# cadiz_mb_20131224.net
KiCad netlist of a schematic drawn in EAGLE
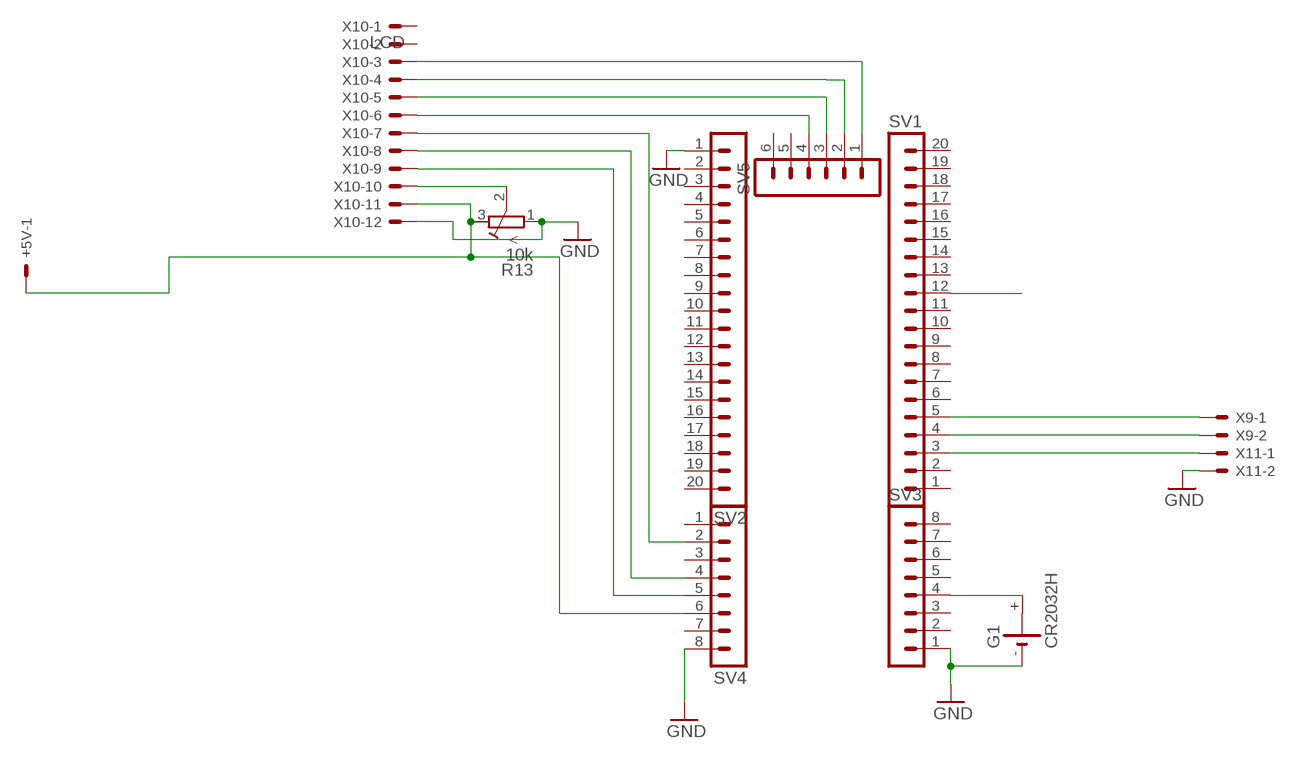
[diagram p0: schematic, sheet 1]

(export (version "E")
  (design (tool "Eeschema 10.0.6"))
  (components
    (comp (ref "+5V")
      (value "22-23-2021")
      (footprint "eagle-import:22-23-2021")
      (fields (field (name "MF") "MOLEX"))
      (libsource (lib "eagle-import") (part "22-23-2021"))
    )
    (comp (ref "G1")
      (value "CR2032H")
      (footprint "eagle-import:CR2032H")
      (libsource (lib "eagle-import") (part "CR2032H"))
    )
    (comp (ref "R13")
      (value "10k")
      (footprint "eagle-import:RTRIM3374")
      (libsource (lib "eagle-import") (part "R-TRIMM3374"))
    )
    (comp (ref "SV1")
      (value "MA20-1")
      (footprint "eagle-import:MA20-1")
      (libsource (lib "eagle-import") (part "MA20-1"))
    )
    (comp (ref "SV2")
      (value "MA20-1")
      (footprint "eagle-import:MA20-1")
      (libsource (lib "eagle-import") (part "MA20-1"))
    )
    (comp (ref "SV3")
      (value "MA08-1")
      (footprint "eagle-import:MA08-1")
      (libsource (lib "eagle-import") (part "MA08-1"))
    )
    (comp (ref "SV4")
      (value "MA08-1")
      (footprint "eagle-import:MA08-1")
      (libsource (lib "eagle-import") (part "MA08-1"))
    )
    (comp (ref "SV5")
      (value "MA06-1")
      (footprint "eagle-import:MA06-1")
      (libsource (lib "eagle-import") (part "MA06-1"))
    )
    (comp (ref "X9")
      (value "22-23-2021")
      (footprint "eagle-import:22-23-2021")
      (fields (field (name "MF") "MOLEX"))
      (libsource (lib "eagle-import") (part "22-23-2021"))
    )
    (comp (ref "X10")
      (value "LCD")
      (footprint "eagle-import:22-23-2121")
      (fields (field (name "MF") "MOLEX") (field (name "MPN") "22-23-2121"))
      (libsource (lib "eagle-import") (part "22-23-2121"))
    )
    (comp (ref "X11")
      (value "22-23-2021")
      (footprint "eagle-import:22-23-2021")
      (fields (field (name "MF") "MOLEX"))
      (libsource (lib "eagle-import") (part "22-23-2021"))
    )
  )
  (nets
    (net (code "1") (name "GND") (class "Default")
      (node (ref "G1") (pin "-") (pinfunction "-_-") (pintype "passive"))
      (node (ref "R13") (pin "1") (pinfunction "E_1") (pintype "passive"))
      (node (ref "SV2") (pin "1") (pinfunction "1_1") (pintype "passive"))
      (node (ref "SV3") (pin "1") (pinfunction "1_1") (pintype "passive"))
      (node (ref "SV4") (pin "8") (pinfunction "8_8") (pintype "passive"))
      (node (ref "X10") (pin "12") (pinfunction "S_12") (pintype "passive"))
      (node (ref "X11") (pin "2") (pinfunction "S_2") (pintype "passive"))
    )
    (net (code "2") (name "Net-(+5VA-S)") (class "Default")
      (node (ref "+5V") (pin "1") (pinfunction "S_1") (pintype "passive"))
      (node (ref "R13") (pin "3") (pinfunction "A_3") (pintype "passive"))
      (node (ref "SV4") (pin "6") (pinfunction "6_6") (pintype "passive"))
      (node (ref "X10") (pin "11") (pinfunction "S_11") (pintype "passive"))
    )
    (net (code "3") (name "Net-(G1-Pad+)") (class "Default")
      (node (ref "G1") (pin "+") (pinfunction "+_+") (pintype "passive"))
      (node (ref "SV3") (pin "4") (pinfunction "4_4") (pintype "passive"))
    )
    (net (code "4") (name "Net-(R13-S)") (class "Default")
      (node (ref "R13") (pin "2") (pinfunction "S_2") (pintype "passive"))
      (node (ref "X10") (pin "10") (pinfunction "S_10") (pintype "passive"))
    )
    (net (code "5") (name "Net-(X9A-S)") (class "Default")
      (node (ref "SV1") (pin "5") (pinfunction "5_5") (pintype "passive"))
      (node (ref "X9") (pin "1") (pinfunction "S_1") (pintype "passive"))
    )
    (net (code "6") (name "Net-(X9B-S)") (class "Default")
      (node (ref "SV1") (pin "4") (pinfunction "4_4") (pintype "passive"))
      (node (ref "X9") (pin "2") (pinfunction "S_2") (pintype "passive"))
    )
    (net (code "7") (name "Net-(X10F-S)") (class "Default")
      (node (ref "SV5") (pin "1") (pinfunction "1_1") (pintype "passive"))
      (node (ref "X10") (pin "3") (pinfunction "S_3") (pintype "passive"))
    )
    (net (code "8") (name "Net-(X10G-S)") (class "Default")
      (node (ref "SV5") (pin "2") (pinfunction "2_2") (pintype "passive"))
      (node (ref "X10") (pin "4") (pinfunction "S_4") (pintype "passive"))
    )
    (net (code "9") (name "Net-(X10H-S)") (class "Default")
      (node (ref "SV5") (pin "3") (pinfunction "3_3") (pintype "passive"))
      (node (ref "X10") (pin "5") (pinfunction "S_5") (pintype "passive"))
    )
    (net (code "10") (name "Net-(X10I-S)") (class "Default")
      (node (ref "SV5") (pin "4") (pinfunction "4_4") (pintype "passive"))
      (node (ref "X10") (pin "6") (pinfunction "S_6") (pintype "passive"))
    )
    (net (code "11") (name "Net-(X10J-S)") (class "Default")
      (node (ref "SV4") (pin "2") (pinfunction "2_2") (pintype "passive"))
      (node (ref "X10") (pin "7") (pinfunction "S_7") (pintype "passive"))
    )
    (net (code "12") (name "Net-(X10K-S)") (class "Default")
      (node (ref "SV4") (pin "4") (pinfunction "4_4") (pintype "passive"))
      (node (ref "X10") (pin "8") (pinfunction "S_8") (pintype "passive"))
    )
    (net (code "13") (name "Net-(X10L-S)") (class "Default")
      (node (ref "SV4") (pin "5") (pinfunction "5_5") (pintype "passive"))
      (node (ref "X10") (pin "9") (pinfunction "S_9") (pintype "passive"))
    )
    (net (code "14") (name "Net-(X11A-S)") (class "Default")
      (node (ref "SV1") (pin "3") (pinfunction "3_3") (pintype "passive"))
      (node (ref "X11") (pin "1") (pinfunction "S_1") (pintype "passive"))
    )
    (net (code "15") (name "unconnected-(G1-+-Pad+@1)") (class "Default")
      (node (ref "G1") (pin "+@1") (pinfunction "+_+@1") (pintype "passive"))
    )
    (net (code "16") (name "unconnected-(SV1-Pad1)") (class "Default")
      (node (ref "SV1") (pin "1") (pinfunction "1_1") (pintype "passive"))
    )
    (net (code "17") (name "unconnected-(SV1-Pad2)") (class "Default")
      (node (ref "SV1") (pin "2") (pinfunction "2_2") (pintype "passive"))
    )
    (net (code "18") (name "unconnected-(SV1-Pad6)") (class "Default")
      (node (ref "SV1") (pin "6") (pinfunction "6_6") (pintype "passive"))
    )
    (net (code "19") (name "unconnected-(SV1-Pad7)") (class "Default")
      (node (ref "SV1") (pin "7") (pinfunction "7_7") (pintype "passive"))
    )
    (net (code "20") (name "unconnected-(SV1-Pad8)") (class "Default")
      (node (ref "SV1") (pin "8") (pinfunction "8_8") (pintype "passive"))
    )
    (net (code "21") (name "unconnected-(SV1-Pad9)") (class "Default")
      (node (ref "SV1") (pin "9") (pinfunction "9_9") (pintype "passive"))
    )
    (net (code "22") (name "unconnected-(SV1-Pad10)") (class "Default")
      (node (ref "SV1") (pin "10") (pinfunction "10_10") (pintype "passive"))
    )
    (net (code "23") (name "unconnected-(SV1-Pad11)") (class "Default")
      (node (ref "SV1") (pin "11") (pinfunction "11_11") (pintype "passive"))
    )
    (net (code "24") (name "unconnected-(SV1-Pad12)") (class "Default")
      (node (ref "SV1") (pin "12") (pinfunction "12_12") (pintype "passive"))
    )
    (net (code "25") (name "unconnected-(SV1-Pad13)") (class "Default")
      (node (ref "SV1") (pin "13") (pinfunction "13_13") (pintype "passive"))
    )
    (net (code "26") (name "unconnected-(SV1-Pad14)") (class "Default")
      (node (ref "SV1") (pin "14") (pinfunction "14_14") (pintype "passive"))
    )
    (net (code "27") (name "unconnected-(SV1-Pad15)") (class "Default")
      (node (ref "SV1") (pin "15") (pinfunction "15_15") (pintype "passive"))
    )
    (net (code "28") (name "unconnected-(SV1-Pad16)") (class "Default")
      (node (ref "SV1") (pin "16") (pinfunction "16_16") (pintype "passive"))
    )
    (net (code "29") (name "unconnected-(SV1-Pad17)") (class "Default")
      (node (ref "SV1") (pin "17") (pinfunction "17_17") (pintype "passive"))
    )
    (net (code "30") (name "unconnected-(SV1-Pad18)") (class "Default")
      (node (ref "SV1") (pin "18") (pinfunction "18_18") (pintype "passive"))
    )
    (net (code "31") (name "unconnected-(SV1-Pad19)") (class "Default")
      (node (ref "SV1") (pin "19") (pinfunction "19_19") (pintype "passive"))
    )
    (net (code "32") (name "unconnected-(SV1-Pad20)") (class "Default")
      (node (ref "SV1") (pin "20") (pinfunction "20_20") (pintype "passive"))
    )
    (net (code "33") (name "unconnected-(SV2-Pad2)") (class "Default")
      (node (ref "SV2") (pin "2") (pinfunction "2_2") (pintype "passive"))
    )
    (net (code "34") (name "unconnected-(SV2-Pad3)") (class "Default")
      (node (ref "SV2") (pin "3") (pinfunction "3_3") (pintype "passive"))
    )
    (net (code "35") (name "unconnected-(SV2-Pad4)") (class "Default")
      (node (ref "SV2") (pin "4") (pinfunction "4_4") (pintype "passive"))
    )
    (net (code "36") (name "unconnected-(SV2-Pad5)") (class "Default")
      (node (ref "SV2") (pin "5") (pinfunction "5_5") (pintype "passive"))
    )
    (net (code "37") (name "unconnected-(SV2-Pad6)") (class "Default")
      (node (ref "SV2") (pin "6") (pinfunction "6_6") (pintype "passive"))
    )
    (net (code "38") (name "unconnected-(SV2-Pad7)") (class "Default")
      (node (ref "SV2") (pin "7") (pinfunction "7_7") (pintype "passive"))
    )
    (net (code "39") (name "unconnected-(SV2-Pad8)") (class "Default")
      (node (ref "SV2") (pin "8") (pinfunction "8_8") (pintype "passive"))
    )
    (net (code "40") (name "unconnected-(SV2-Pad9)") (class "Default")
      (node (ref "SV2") (pin "9") (pinfunction "9_9") (pintype "passive"))
    )
    (net (code "41") (name "unconnected-(SV2-Pad10)") (class "Default")
      (node (ref "SV2") (pin "10") (pinfunction "10_10") (pintype "passive"))
    )
    (net (code "42") (name "unconnected-(SV2-Pad11)") (class "Default")
      (node (ref "SV2") (pin "11") (pinfunction "11_11") (pintype "passive"))
    )
    (net (code "43") (name "unconnected-(SV2-Pad12)") (class "Default")
      (node (ref "SV2") (pin "12") (pinfunction "12_12") (pintype "passive"))
    )
    (net (code "44") (name "unconnected-(SV2-Pad13)") (class "Default")
      (node (ref "SV2") (pin "13") (pinfunction "13_13") (pintype "passive"))
    )
    (net (code "45") (name "unconnected-(SV2-Pad14)") (class "Default")
      (node (ref "SV2") (pin "14") (pinfunction "14_14") (pintype "passive"))
    )
    (net (code "46") (name "unconnected-(SV2-Pad15)") (class "Default")
      (node (ref "SV2") (pin "15") (pinfunction "15_15") (pintype "passive"))
    )
    (net (code "47") (name "unconnected-(SV2-Pad16)") (class "Default")
      (node (ref "SV2") (pin "16") (pinfunction "16_16") (pintype "passive"))
    )
    (net (code "48") (name "unconnected-(SV2-Pad17)") (class "Default")
      (node (ref "SV2") (pin "17") (pinfunction "17_17") (pintype "passive"))
    )
    (net (code "49") (name "unconnected-(SV2-Pad18)") (class "Default")
      (node (ref "SV2") (pin "18") (pinfunction "18_18") (pintype "passive"))
    )
    (net (code "50") (name "unconnected-(SV2-Pad19)") (class "Default")
      (node (ref "SV2") (pin "19") (pinfunction "19_19") (pintype "passive"))
    )
    (net (code "51") (name "unconnected-(SV2-Pad20)") (class "Default")
      (node (ref "SV2") (pin "20") (pinfunction "20_20") (pintype "passive"))
    )
    (net (code "52") (name "unconnected-(SV3-Pad2)") (class "Default")
      (node (ref "SV3") (pin "2") (pinfunction "2_2") (pintype "passive"))
    )
    (net (code "53") (name "unconnected-(SV3-Pad3)") (class "Default")
      (node (ref "SV3") (pin "3") (pinfunction "3_3") (pintype "passive"))
    )
    (net (code "54") (name "unconnected-(SV3-Pad5)") (class "Default")
      (node (ref "SV3") (pin "5") (pinfunction "5_5") (pintype "passive"))
    )
    (net (code "55") (name "unconnected-(SV3-Pad6)") (class "Default")
      (node (ref "SV3") (pin "6") (pinfunction "6_6") (pintype "passive"))
    )
    (net (code "56") (name "unconnected-(SV3-Pad7)") (class "Default")
      (node (ref "SV3") (pin "7") (pinfunction "7_7") (pintype "passive"))
    )
    (net (code "57") (name "unconnected-(SV3-Pad8)") (class "Default")
      (node (ref "SV3") (pin "8") (pinfunction "8_8") (pintype "passive"))
    )
    (net (code "58") (name "unconnected-(SV4-Pad1)") (class "Default")
      (node (ref "SV4") (pin "1") (pinfunction "1_1") (pintype "passive"))
    )
    (net (code "59") (name "unconnected-(SV4-Pad3)") (class "Default")
      (node (ref "SV4") (pin "3") (pinfunction "3_3") (pintype "passive"))
    )
    (net (code "60") (name "unconnected-(SV4-Pad7)") (class "Default")
      (node (ref "SV4") (pin "7") (pinfunction "7_7") (pintype "passive"))
    )
    (net (code "61") (name "unconnected-(SV5-Pad5)") (class "Default")
      (node (ref "SV5") (pin "5") (pinfunction "5_5") (pintype "passive"))
    )
    (net (code "62") (name "unconnected-(SV5-Pad6)") (class "Default")
      (node (ref "SV5") (pin "6") (pinfunction "6_6") (pintype "passive"))
    )
    (net (code "63") (name "unconnected-(X10A-S-Pad1)") (class "Default")
      (node (ref "X10") (pin "1") (pinfunction "S_1") (pintype "passive"))
    )
    (net (code "64") (name "unconnected-(X10E-S-Pad2)") (class "Default")
      (node (ref "X10") (pin "2") (pinfunction "S_2") (pintype "passive"))
    )
  )
)
